# thermocouple.net
KiCad netlist of a schematic drawn in Altium Designer
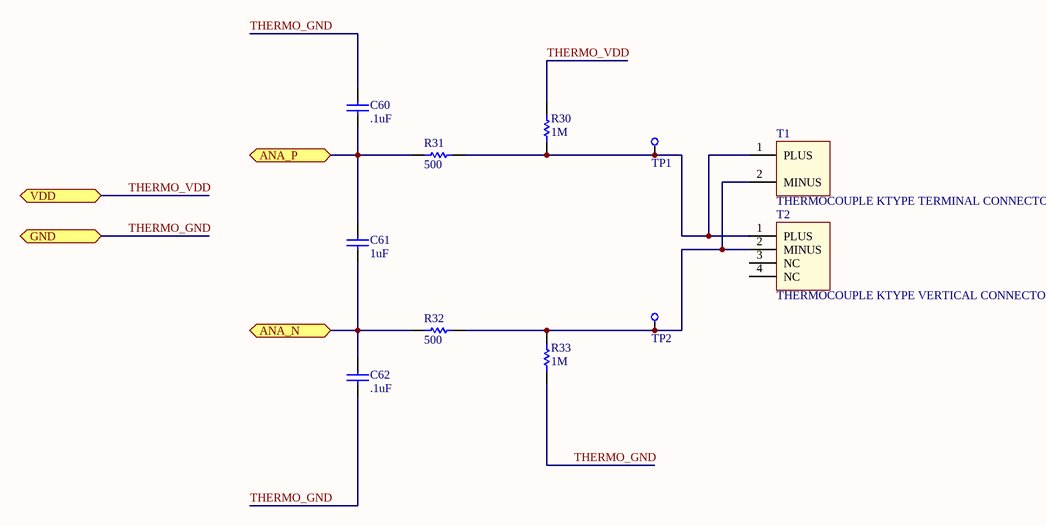
[diagram p0: thermocouple.SchDoc]

(export (version "E")
  (design (tool "Eeschema 10.0.6"))
  (components
    (comp (ref "C60")
      (value ".1uF")
      (footprint "0805")
      (fields (field (name "TOLERANCE") "5%") (field (name "VOLTAGE") "10V") (field (name "Comment") "CAP"))
      (libsource (lib "gasctrl") (part "CAP"))
    )
    (comp (ref "C61")
      (value "1uF")
      (footprint "0805")
      (fields (field (name "TOLERANCE") "5%") (field (name "VOLTAGE") "10V") (field (name "Comment") "CAP"))
      (libsource (lib "gasctrl") (part "CAP"))
    )
    (comp (ref "C62")
      (value ".1uF")
      (footprint "0805")
      (fields (field (name "TOLERANCE") "5%") (field (name "VOLTAGE") "10V") (field (name "Comment") "CAP"))
      (libsource (lib "gasctrl") (part "CAP"))
    )
    (comp (ref "R30")
      (value "1M")
      (footprint "0805")
      (fields (field (name "TOLERANCE") "5%") (field (name "Comment") "RES"))
      (libsource (lib "gasctrl") (part "RES"))
    )
    (comp (ref "R31")
      (value "500")
      (footprint "0805")
      (fields (field (name "TOLERANCE") "5%") (field (name "Comment") "RES"))
      (libsource (lib "gasctrl") (part "RES"))
    )
    (comp (ref "R32")
      (value "500")
      (footprint "0805")
      (fields (field (name "TOLERANCE") "5%") (field (name "Comment") "RES"))
      (libsource (lib "gasctrl") (part "RES"))
    )
    (comp (ref "R33")
      (value "1M")
      (footprint "0805")
      (fields (field (name "TOLERANCE") "5%") (field (name "Comment") "RES"))
      (libsource (lib "gasctrl") (part "RES"))
    )
    (comp (ref "T1")
      (value "THERMOCOUPLE KTYPE TERMINAL CONNECTOR")
      (footprint "MKDSN2")
      (libsource (lib "gasctrl") (part "THERMOCOUPLE TERMINAL"))
    )
    (comp (ref "T2")
      (value "THERMOCOUPLE KTYPE VERTICAL CONNECTOR")
      (footprint "PCC-SMP-V-K")
      (fields (field (name "MANUFACTURER") "Newport"))
      (libsource (lib "gasctrl") (part "THERMOCOUPLE"))
    )
    (comp (ref "TP1")
      (value "TEST_POINT")
      (footprint "gasctrl:TEST_POINT")
      (description "Thruhole Miniature Test Point")
      (fields (field (name "MANUFACTURER") "Keystone Electronics Corp"))
      (libsource (lib "gasctrl") (part "TEST_POINT"))
    )
    (comp (ref "TP2")
      (value "TEST_POINT")
      (footprint "gasctrl:TEST_POINT")
      (description "Thruhole Miniature Test Point")
      (fields (field (name "MANUFACTURER") "Keystone Electronics Corp"))
      (libsource (lib "gasctrl") (part "TEST_POINT"))
    )
  )
  (nets
    (net (code "1") (name "/ANA_N") (class "Default")
      (node (ref "C61") (pin "1") (pinfunction "1_1") (pintype "passive"))
      (node (ref "C62") (pin "2") (pinfunction "2_2") (pintype "passive"))
      (node (ref "R32") (pin "1") (pinfunction "1_1") (pintype "passive"))
    )
    (net (code "2") (name "/ANA_P") (class "Default")
      (node (ref "C60") (pin "1") (pinfunction "1_1") (pintype "passive"))
      (node (ref "C61") (pin "2") (pinfunction "2_2") (pintype "passive"))
      (node (ref "R31") (pin "2") (pinfunction "2_2") (pintype "passive"))
    )
    (net (code "3") (name "/THERMO_GND") (class "Default")
      (node (ref "C60") (pin "2") (pinfunction "2_2") (pintype "passive"))
      (node (ref "C62") (pin "1") (pinfunction "1_1") (pintype "passive"))
      (node (ref "R33") (pin "1") (pinfunction "1_1") (pintype "passive"))
    )
    (net (code "4") (name "/THERMO_VDD") (class "Default")
      (node (ref "R30") (pin "2") (pinfunction "2_2") (pintype "passive"))
    )
    (net (code "5") (name "Net-(T1-MINUS)") (class "Default")
      (node (ref "R32") (pin "2") (pinfunction "2_2") (pintype "passive"))
      (node (ref "R33") (pin "2") (pinfunction "2_2") (pintype "passive"))
      (node (ref "T1") (pin "2") (pinfunction "MINUS_2") (pintype "passive"))
      (node (ref "T2") (pin "2") (pinfunction "MINUS_2") (pintype "passive"))
      (node (ref "TP2") (pin "1") (pinfunction "1_1") (pintype "passive"))
    )
    (net (code "6") (name "Net-(T1-PLUS)") (class "Default")
      (node (ref "R30") (pin "1") (pinfunction "1_1") (pintype "passive"))
      (node (ref "R31") (pin "1") (pinfunction "1_1") (pintype "passive"))
      (node (ref "T1") (pin "1") (pinfunction "PLUS_1") (pintype "passive"))
      (node (ref "T2") (pin "1") (pinfunction "PLUS_1") (pintype "passive"))
      (node (ref "TP1") (pin "1") (pinfunction "1_1") (pintype "passive"))
    )
    (net (code "7") (name "unconnected-(T2-NC-Pad3)") (class "Default")
      (node (ref "T2") (pin "3") (pinfunction "NC_3") (pintype "passive"))
    )
    (net (code "8") (name "unconnected-(T2-NC-Pad4)") (class "Default")
      (node (ref "T2") (pin "4") (pinfunction "NC_4") (pintype "passive"))
    )
  )
)
